# ModMoPSS_-_IR_receiver.net
KiCad netlist of a schematic drawn in EAGLE
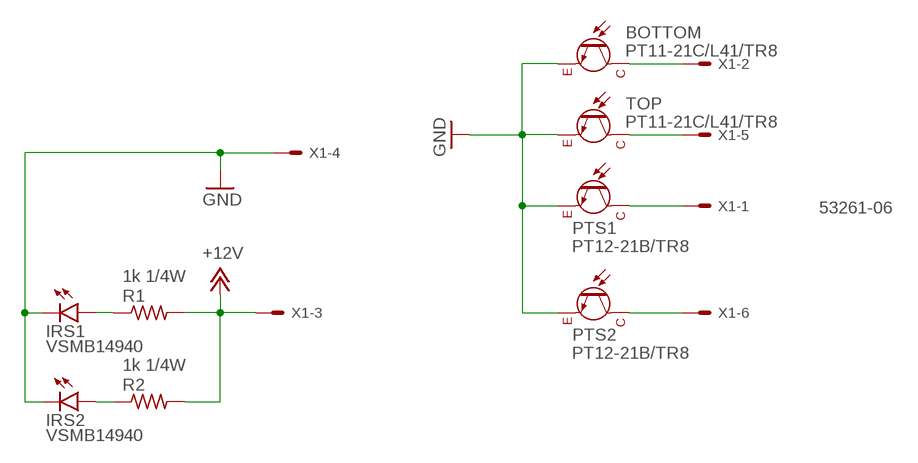
[diagram p0: schematic, sheet 1]

(export (version "E")
  (design (tool "Eeschema 10.0.6"))
  (components
    (comp (ref "BOTTOM")
      (value "PT11-21C/L41/TR8")
      (footprint "eagle-import:CHIPLED_1206")
      (libsource (lib "eagle-import") (part "PT11-21C/L41/TR8"))
    )
    (comp (ref "IRS1")
      (value "VSMB14940")
      (footprint "eagle-import:VSMB14940")
      (libsource (lib "eagle-import") (part "VSMB14940"))
    )
    (comp (ref "IRS2")
      (value "VSMB14940")
      (footprint "eagle-import:VSMB14940")
      (libsource (lib "eagle-import") (part "VSMB14940"))
    )
    (comp (ref "PTS1")
      (value "PT12-21B/TR8")
      (footprint "eagle-import:PT12-21B_TR8")
      (libsource (lib "eagle-import") (part "PT12-21B/TR8"))
    )
    (comp (ref "PTS2")
      (value "PT12-21B/TR8")
      (footprint "eagle-import:PT12-21B_TR8")
      (libsource (lib "eagle-import") (part "PT12-21B/TR8"))
    )
    (comp (ref "R1")
      (value "1k 1/4W")
      (footprint "eagle-import:R0805")
      (libsource (lib "eagle-import") (part "R-US_R0805"))
    )
    (comp (ref "R2")
      (value "1k 1/4W")
      (footprint "eagle-import:R0805")
      (libsource (lib "eagle-import") (part "R-US_R0805"))
    )
    (comp (ref "TOP")
      (value "PT11-21C/L41/TR8")
      (footprint "eagle-import:CHIPLED_1206")
      (libsource (lib "eagle-import") (part "PT11-21C/L41/TR8"))
    )
    (comp (ref "X1")
      (value "53261-06")
      (footprint "eagle-import:53261-06")
      (fields (field (name "MF") "MOLEX"))
      (libsource (lib "eagle-import") (part "53?-06261"))
    )
  )
  (nets
    (net (code "1") (name "+12V") (class "Default")
      (node (ref "R1") (pin "2") (pinfunction "2_2") (pintype "passive"))
      (node (ref "R2") (pin "2") (pinfunction "2_2") (pintype "passive"))
      (node (ref "X1") (pin "3") (pinfunction "S_3") (pintype "passive"))
    )
    (net (code "2") (name "GND") (class "Default")
      (node (ref "BOTTOM") (pin "A") (pinfunction "E_A") (pintype "passive"))
      (node (ref "IRS1") (pin "P$2") (pinfunction "C_P$2") (pintype "passive"))
      (node (ref "IRS2") (pin "P$2") (pinfunction "C_P$2") (pintype "passive"))
      (node (ref "PTS1") (pin "P$2") (pinfunction "E_P$2") (pintype "passive"))
      (node (ref "PTS2") (pin "P$2") (pinfunction "E_P$2") (pintype "passive"))
      (node (ref "TOP") (pin "A") (pinfunction "E_A") (pintype "passive"))
      (node (ref "X1") (pin "4") (pinfunction "S_4") (pintype "passive"))
    )
    (net (code "3") (name "Net-(IRS1-A)") (class "Default")
      (node (ref "IRS1") (pin "P$1") (pinfunction "A_P$1") (pintype "passive"))
      (node (ref "R1") (pin "1") (pinfunction "1_1") (pintype "passive"))
    )
    (net (code "4") (name "Net-(IRS2-A)") (class "Default")
      (node (ref "IRS2") (pin "P$1") (pinfunction "A_P$1") (pintype "passive"))
      (node (ref "R2") (pin "1") (pinfunction "1_1") (pintype "passive"))
    )
    (net (code "5") (name "Net-(PTS1-C)") (class "Default")
      (node (ref "PTS1") (pin "P$1") (pinfunction "C_P$1") (pintype "passive"))
      (node (ref "X1") (pin "1") (pinfunction "S_1") (pintype "passive"))
    )
    (net (code "6") (name "Net-(PTS2-C)") (class "Default")
      (node (ref "PTS2") (pin "P$1") (pinfunction "C_P$1") (pintype "passive"))
      (node (ref "X1") (pin "6") (pinfunction "S_6") (pintype "passive"))
    )
    (net (code "7") (name "Net-(X1B-S)") (class "Default")
      (node (ref "BOTTOM") (pin "C") (pinfunction "C_C") (pintype "passive"))
      (node (ref "X1") (pin "2") (pinfunction "S_2") (pintype "passive"))
    )
    (net (code "8") (name "Net-(X1E-S)") (class "Default")
      (node (ref "TOP") (pin "C") (pinfunction "C_C") (pintype "passive"))
      (node (ref "X1") (pin "5") (pinfunction "S_5") (pintype "passive"))
    )
  )
)
